# Led_Panel.net
KiCad netlist of a schematic drawn in Altium Designer
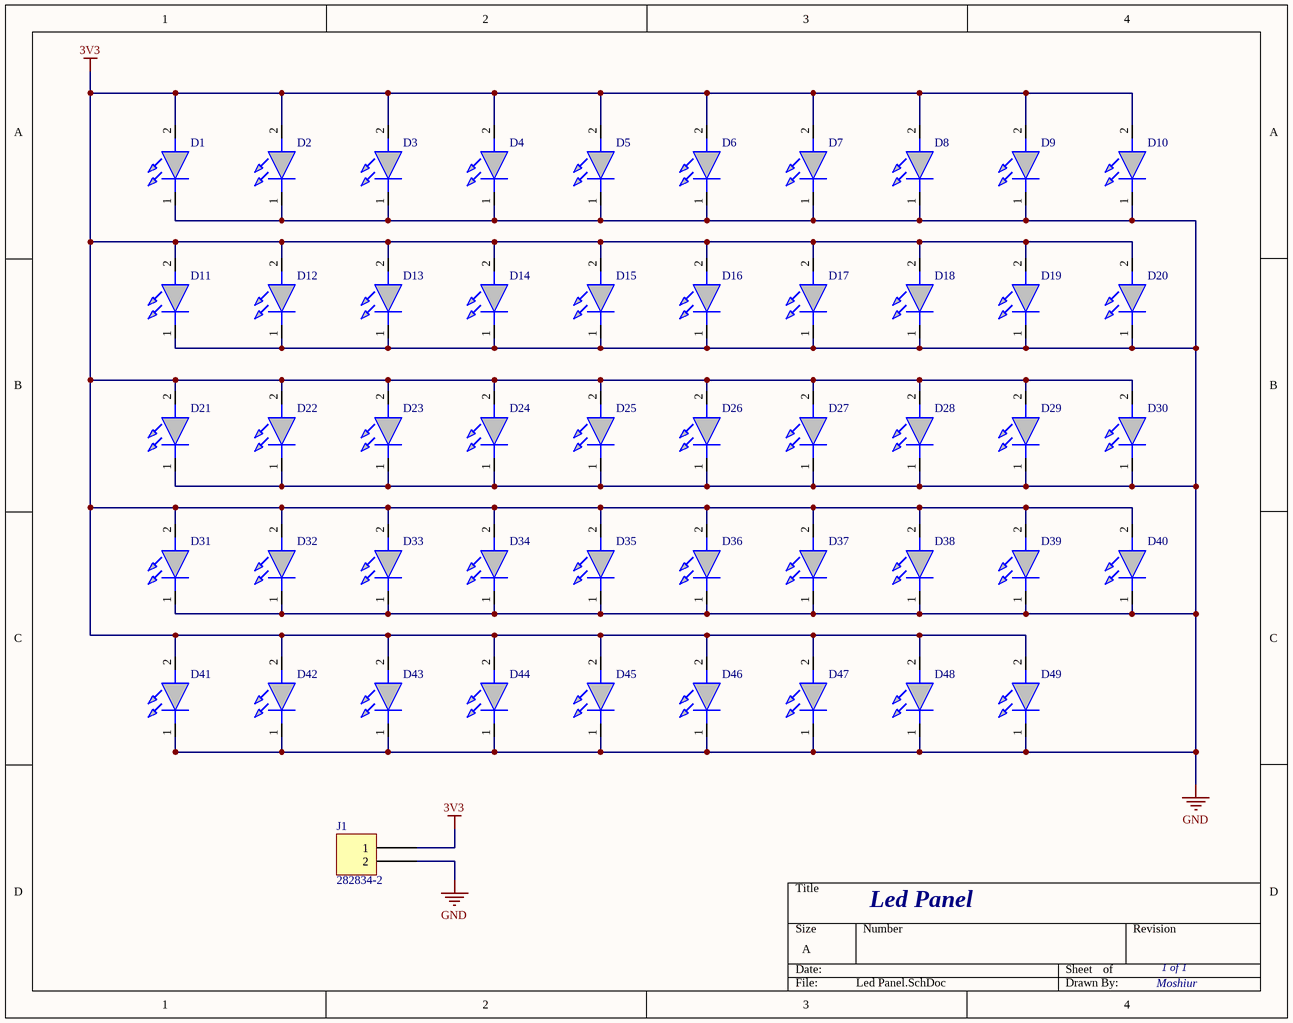
[diagram p0: Led Panel.SchDoc]

(export (version "E")
  (design (tool "Eeschema 10.0.6"))
  (components
    (comp (ref "D1")
      (value "L1IG-0750100000000")
      (footprint "L1IG0750100000000")
      (description "Infrared Emitters - High Power Broadrange IR LED 600 - 1050nm")
      (fields (field (name "MOUSER PART NUMBER") "997-L1IG075010000"))
      (libsource (lib "L1IG-0750100000000") (part "L1IG-0750100000000"))
    )
    (comp (ref "D2")
      (value "L1IG-0750100000000")
      (footprint "L1IG0750100000000")
      (description "Infrared Emitters - High Power Broadrange IR LED 600 - 1050nm")
      (fields (field (name "MOUSER PART NUMBER") "997-L1IG075010000"))
      (libsource (lib "L1IG-0750100000000") (part "L1IG-0750100000000"))
    )
    (comp (ref "D3")
      (value "L1IG-0750100000000")
      (footprint "L1IG0750100000000")
      (description "Infrared Emitters - High Power Broadrange IR LED 600 - 1050nm")
      (fields (field (name "MOUSER PART NUMBER") "997-L1IG075010000"))
      (libsource (lib "L1IG-0750100000000") (part "L1IG-0750100000000"))
    )
    (comp (ref "D4")
      (value "L1IG-0750100000000")
      (footprint "L1IG0750100000000")
      (description "Infrared Emitters - High Power Broadrange IR LED 600 - 1050nm")
      (fields (field (name "MOUSER PART NUMBER") "997-L1IG075010000"))
      (libsource (lib "L1IG-0750100000000") (part "L1IG-0750100000000"))
    )
    (comp (ref "D5")
      (value "L1IG-0750100000000")
      (footprint "L1IG0750100000000")
      (description "Infrared Emitters - High Power Broadrange IR LED 600 - 1050nm")
      (fields (field (name "MOUSER PART NUMBER") "997-L1IG075010000"))
      (libsource (lib "L1IG-0750100000000") (part "L1IG-0750100000000"))
    )
    (comp (ref "D6")
      (value "L1IG-0750100000000")
      (footprint "L1IG0750100000000")
      (description "Infrared Emitters - High Power Broadrange IR LED 600 - 1050nm")
      (fields (field (name "MOUSER PART NUMBER") "997-L1IG075010000"))
      (libsource (lib "L1IG-0750100000000") (part "L1IG-0750100000000"))
    )
    (comp (ref "D7")
      (value "L1IG-0750100000000")
      (footprint "L1IG0750100000000")
      (description "Infrared Emitters - High Power Broadrange IR LED 600 - 1050nm")
      (fields (field (name "MOUSER PART NUMBER") "997-L1IG075010000"))
      (libsource (lib "L1IG-0750100000000") (part "L1IG-0750100000000"))
    )
    (comp (ref "D8")
      (value "L1IG-0750100000000")
      (footprint "L1IG0750100000000")
      (description "Infrared Emitters - High Power Broadrange IR LED 600 - 1050nm")
      (fields (field (name "MOUSER PART NUMBER") "997-L1IG075010000"))
      (libsource (lib "L1IG-0750100000000") (part "L1IG-0750100000000"))
    )
    (comp (ref "D9")
      (value "L1IG-0750100000000")
      (footprint "L1IG0750100000000")
      (description "Infrared Emitters - High Power Broadrange IR LED 600 - 1050nm")
      (fields (field (name "MOUSER PART NUMBER") "997-L1IG075010000"))
      (libsource (lib "L1IG-0750100000000") (part "L1IG-0750100000000"))
    )
    (comp (ref "D10")
      (value "L1IG-0750100000000")
      (footprint "L1IG0750100000000")
      (description "Infrared Emitters - High Power Broadrange IR LED 600 - 1050nm")
      (fields (field (name "MOUSER PART NUMBER") "997-L1IG075010000"))
      (libsource (lib "L1IG-0750100000000") (part "L1IG-0750100000000"))
    )
    (comp (ref "D11")
      (value "L1IG-0750100000000")
      (footprint "L1IG0750100000000")
      (description "Infrared Emitters - High Power Broadrange IR LED 600 - 1050nm")
      (fields (field (name "MOUSER PART NUMBER") "997-L1IG075010000"))
      (libsource (lib "L1IG-0750100000000") (part "L1IG-0750100000000"))
    )
    (comp (ref "D12")
      (value "L1IG-0750100000000")
      (footprint "L1IG0750100000000")
      (description "Infrared Emitters - High Power Broadrange IR LED 600 - 1050nm")
      (fields (field (name "MOUSER PART NUMBER") "997-L1IG075010000"))
      (libsource (lib "L1IG-0750100000000") (part "L1IG-0750100000000"))
    )
    (comp (ref "D13")
      (value "L1IG-0750100000000")
      (footprint "L1IG0750100000000")
      (description "Infrared Emitters - High Power Broadrange IR LED 600 - 1050nm")
      (fields (field (name "MOUSER PART NUMBER") "997-L1IG075010000"))
      (libsource (lib "L1IG-0750100000000") (part "L1IG-0750100000000"))
    )
    (comp (ref "D14")
      (value "L1IG-0750100000000")
      (footprint "L1IG0750100000000")
      (description "Infrared Emitters - High Power Broadrange IR LED 600 - 1050nm")
      (fields (field (name "MOUSER PART NUMBER") "997-L1IG075010000"))
      (libsource (lib "L1IG-0750100000000") (part "L1IG-0750100000000"))
    )
    (comp (ref "D15")
      (value "L1IG-0750100000000")
      (footprint "L1IG0750100000000")
      (description "Infrared Emitters - High Power Broadrange IR LED 600 - 1050nm")
      (fields (field (name "MOUSER PART NUMBER") "997-L1IG075010000"))
      (libsource (lib "L1IG-0750100000000") (part "L1IG-0750100000000"))
    )
    (comp (ref "D16")
      (value "L1IG-0750100000000")
      (footprint "L1IG0750100000000")
      (description "Infrared Emitters - High Power Broadrange IR LED 600 - 1050nm")
      (fields (field (name "MOUSER PART NUMBER") "997-L1IG075010000"))
      (libsource (lib "L1IG-0750100000000") (part "L1IG-0750100000000"))
    )
    (comp (ref "D17")
      (value "L1IG-0750100000000")
      (footprint "L1IG0750100000000")
      (description "Infrared Emitters - High Power Broadrange IR LED 600 - 1050nm")
      (fields (field (name "MOUSER PART NUMBER") "997-L1IG075010000"))
      (libsource (lib "L1IG-0750100000000") (part "L1IG-0750100000000"))
    )
    (comp (ref "D18")
      (value "L1IG-0750100000000")
      (footprint "L1IG0750100000000")
      (description "Infrared Emitters - High Power Broadrange IR LED 600 - 1050nm")
      (fields (field (name "MOUSER PART NUMBER") "997-L1IG075010000"))
      (libsource (lib "L1IG-0750100000000") (part "L1IG-0750100000000"))
    )
    (comp (ref "D19")
      (value "L1IG-0750100000000")
      (footprint "L1IG0750100000000")
      (description "Infrared Emitters - High Power Broadrange IR LED 600 - 1050nm")
      (fields (field (name "MOUSER PART NUMBER") "997-L1IG075010000"))
      (libsource (lib "L1IG-0750100000000") (part "L1IG-0750100000000"))
    )
    (comp (ref "D20")
      (value "L1IG-0750100000000")
      (footprint "L1IG0750100000000")
      (description "Infrared Emitters - High Power Broadrange IR LED 600 - 1050nm")
      (fields (field (name "MOUSER PART NUMBER") "997-L1IG075010000"))
      (libsource (lib "L1IG-0750100000000") (part "L1IG-0750100000000"))
    )
    (comp (ref "D21")
      (value "L1IG-0750100000000")
      (footprint "L1IG0750100000000")
      (description "Infrared Emitters - High Power Broadrange IR LED 600 - 1050nm")
      (fields (field (name "MOUSER PART NUMBER") "997-L1IG075010000"))
      (libsource (lib "L1IG-0750100000000") (part "L1IG-0750100000000"))
    )
    (comp (ref "D22")
      (value "L1IG-0750100000000")
      (footprint "L1IG0750100000000")
      (description "Infrared Emitters - High Power Broadrange IR LED 600 - 1050nm")
      (fields (field (name "MOUSER PART NUMBER") "997-L1IG075010000"))
      (libsource (lib "L1IG-0750100000000") (part "L1IG-0750100000000"))
    )
    (comp (ref "D23")
      (value "L1IG-0750100000000")
      (footprint "L1IG0750100000000")
      (description "Infrared Emitters - High Power Broadrange IR LED 600 - 1050nm")
      (fields (field (name "MOUSER PART NUMBER") "997-L1IG075010000"))
      (libsource (lib "L1IG-0750100000000") (part "L1IG-0750100000000"))
    )
    (comp (ref "D24")
      (value "L1IG-0750100000000")
      (footprint "L1IG0750100000000")
      (description "Infrared Emitters - High Power Broadrange IR LED 600 - 1050nm")
      (fields (field (name "MOUSER PART NUMBER") "997-L1IG075010000"))
      (libsource (lib "L1IG-0750100000000") (part "L1IG-0750100000000"))
    )
    (comp (ref "D25")
      (value "L1IG-0750100000000")
      (footprint "L1IG0750100000000")
      (description "Infrared Emitters - High Power Broadrange IR LED 600 - 1050nm")
      (fields (field (name "MOUSER PART NUMBER") "997-L1IG075010000"))
      (libsource (lib "L1IG-0750100000000") (part "L1IG-0750100000000"))
    )
    (comp (ref "D26")
      (value "L1IG-0750100000000")
      (footprint "L1IG0750100000000")
      (description "Infrared Emitters - High Power Broadrange IR LED 600 - 1050nm")
      (fields (field (name "MOUSER PART NUMBER") "997-L1IG075010000"))
      (libsource (lib "L1IG-0750100000000") (part "L1IG-0750100000000"))
    )
    (comp (ref "D27")
      (value "L1IG-0750100000000")
      (footprint "L1IG0750100000000")
      (description "Infrared Emitters - High Power Broadrange IR LED 600 - 1050nm")
      (fields (field (name "MOUSER PART NUMBER") "997-L1IG075010000"))
      (libsource (lib "L1IG-0750100000000") (part "L1IG-0750100000000"))
    )
    (comp (ref "D28")
      (value "L1IG-0750100000000")
      (footprint "L1IG0750100000000")
      (description "Infrared Emitters - High Power Broadrange IR LED 600 - 1050nm")
      (fields (field (name "MOUSER PART NUMBER") "997-L1IG075010000"))
      (libsource (lib "L1IG-0750100000000") (part "L1IG-0750100000000"))
    )
    (comp (ref "D29")
      (value "L1IG-0750100000000")
      (footprint "L1IG0750100000000")
      (description "Infrared Emitters - High Power Broadrange IR LED 600 - 1050nm")
      (fields (field (name "MOUSER PART NUMBER") "997-L1IG075010000"))
      (libsource (lib "L1IG-0750100000000") (part "L1IG-0750100000000"))
    )
    (comp (ref "D30")
      (value "L1IG-0750100000000")
      (footprint "L1IG0750100000000")
      (description "Infrared Emitters - High Power Broadrange IR LED 600 - 1050nm")
      (fields (field (name "MOUSER PART NUMBER") "997-L1IG075010000"))
      (libsource (lib "L1IG-0750100000000") (part "L1IG-0750100000000"))
    )
    (comp (ref "D31")
      (value "L1IG-0750100000000")
      (footprint "L1IG0750100000000")
      (description "Infrared Emitters - High Power Broadrange IR LED 600 - 1050nm")
      (fields (field (name "MOUSER PART NUMBER") "997-L1IG075010000"))
      (libsource (lib "L1IG-0750100000000") (part "L1IG-0750100000000"))
    )
    (comp (ref "D32")
      (value "L1IG-0750100000000")
      (footprint "L1IG0750100000000")
      (description "Infrared Emitters - High Power Broadrange IR LED 600 - 1050nm")
      (fields (field (name "MOUSER PART NUMBER") "997-L1IG075010000"))
      (libsource (lib "L1IG-0750100000000") (part "L1IG-0750100000000"))
    )
    (comp (ref "D33")
      (value "L1IG-0750100000000")
      (footprint "L1IG0750100000000")
      (description "Infrared Emitters - High Power Broadrange IR LED 600 - 1050nm")
      (fields (field (name "MOUSER PART NUMBER") "997-L1IG075010000"))
      (libsource (lib "L1IG-0750100000000") (part "L1IG-0750100000000"))
    )
    (comp (ref "D34")
      (value "L1IG-0750100000000")
      (footprint "L1IG0750100000000")
      (description "Infrared Emitters - High Power Broadrange IR LED 600 - 1050nm")
      (fields (field (name "MOUSER PART NUMBER") "997-L1IG075010000"))
      (libsource (lib "L1IG-0750100000000") (part "L1IG-0750100000000"))
    )
    (comp (ref "D35")
      (value "L1IG-0750100000000")
      (footprint "L1IG0750100000000")
      (description "Infrared Emitters - High Power Broadrange IR LED 600 - 1050nm")
      (fields (field (name "MOUSER PART NUMBER") "997-L1IG075010000"))
      (libsource (lib "L1IG-0750100000000") (part "L1IG-0750100000000"))
    )
    (comp (ref "D36")
      (value "L1IG-0750100000000")
      (footprint "L1IG0750100000000")
      (description "Infrared Emitters - High Power Broadrange IR LED 600 - 1050nm")
      (fields (field (name "MOUSER PART NUMBER") "997-L1IG075010000"))
      (libsource (lib "L1IG-0750100000000") (part "L1IG-0750100000000"))
    )
    (comp (ref "D37")
      (value "L1IG-0750100000000")
      (footprint "L1IG0750100000000")
      (description "Infrared Emitters - High Power Broadrange IR LED 600 - 1050nm")
      (fields (field (name "MOUSER PART NUMBER") "997-L1IG075010000"))
      (libsource (lib "L1IG-0750100000000") (part "L1IG-0750100000000"))
    )
    (comp (ref "D38")
      (value "L1IG-0750100000000")
      (footprint "L1IG0750100000000")
      (description "Infrared Emitters - High Power Broadrange IR LED 600 - 1050nm")
      (fields (field (name "MOUSER PART NUMBER") "997-L1IG075010000"))
      (libsource (lib "L1IG-0750100000000") (part "L1IG-0750100000000"))
    )
    (comp (ref "D39")
      (value "L1IG-0750100000000")
      (footprint "L1IG0750100000000")
      (description "Infrared Emitters - High Power Broadrange IR LED 600 - 1050nm")
      (fields (field (name "MOUSER PART NUMBER") "997-L1IG075010000"))
      (libsource (lib "L1IG-0750100000000") (part "L1IG-0750100000000"))
    )
    (comp (ref "D40")
      (value "L1IG-0750100000000")
      (footprint "L1IG0750100000000")
      (description "Infrared Emitters - High Power Broadrange IR LED 600 - 1050nm")
      (fields (field (name "MOUSER PART NUMBER") "997-L1IG075010000"))
      (libsource (lib "L1IG-0750100000000") (part "L1IG-0750100000000"))
    )
    (comp (ref "D41")
      (value "L1IG-0750100000000")
      (footprint "L1IG0750100000000")
      (description "Infrared Emitters - High Power Broadrange IR LED 600 - 1050nm")
      (fields (field (name "MOUSER PART NUMBER") "997-L1IG075010000"))
      (libsource (lib "L1IG-0750100000000") (part "L1IG-0750100000000"))
    )
    (comp (ref "D42")
      (value "L1IG-0750100000000")
      (footprint "L1IG0750100000000")
      (description "Infrared Emitters - High Power Broadrange IR LED 600 - 1050nm")
      (fields (field (name "MOUSER PART NUMBER") "997-L1IG075010000"))
      (libsource (lib "L1IG-0750100000000") (part "L1IG-0750100000000"))
    )
    (comp (ref "D43")
      (value "L1IG-0750100000000")
      (footprint "L1IG0750100000000")
      (description "Infrared Emitters - High Power Broadrange IR LED 600 - 1050nm")
      (fields (field (name "MOUSER PART NUMBER") "997-L1IG075010000"))
      (libsource (lib "L1IG-0750100000000") (part "L1IG-0750100000000"))
    )
    (comp (ref "D44")
      (value "L1IG-0750100000000")
      (footprint "L1IG0750100000000")
      (description "Infrared Emitters - High Power Broadrange IR LED 600 - 1050nm")
      (fields (field (name "MOUSER PART NUMBER") "997-L1IG075010000"))
      (libsource (lib "L1IG-0750100000000") (part "L1IG-0750100000000"))
    )
    (comp (ref "D45")
      (value "L1IG-0750100000000")
      (footprint "L1IG0750100000000")
      (description "Infrared Emitters - High Power Broadrange IR LED 600 - 1050nm")
      (fields (field (name "MOUSER PART NUMBER") "997-L1IG075010000"))
      (libsource (lib "L1IG-0750100000000") (part "L1IG-0750100000000"))
    )
    (comp (ref "D46")
      (value "L1IG-0750100000000")
      (footprint "L1IG0750100000000")
      (description "Infrared Emitters - High Power Broadrange IR LED 600 - 1050nm")
      (fields (field (name "MOUSER PART NUMBER") "997-L1IG075010000"))
      (libsource (lib "L1IG-0750100000000") (part "L1IG-0750100000000"))
    )
    (comp (ref "D47")
      (value "L1IG-0750100000000")
      (footprint "L1IG0750100000000")
      (description "Infrared Emitters - High Power Broadrange IR LED 600 - 1050nm")
      (fields (field (name "MOUSER PART NUMBER") "997-L1IG075010000"))
      (libsource (lib "L1IG-0750100000000") (part "L1IG-0750100000000"))
    )
    (comp (ref "D48")
      (value "L1IG-0750100000000")
      (footprint "L1IG0750100000000")
      (description "Infrared Emitters - High Power Broadrange IR LED 600 - 1050nm")
      (fields (field (name "MOUSER PART NUMBER") "997-L1IG075010000"))
      (libsource (lib "L1IG-0750100000000") (part "L1IG-0750100000000"))
    )
    (comp (ref "D49")
      (value "L1IG-0750100000000")
      (footprint "L1IG0750100000000")
      (description "Infrared Emitters - High Power Broadrange IR LED 600 - 1050nm")
      (fields (field (name "MOUSER PART NUMBER") "997-L1IG075010000"))
      (libsource (lib "L1IG-0750100000000") (part "L1IG-0750100000000"))
    )
    (comp (ref "J1")
      (value "282834-2")
      (footprint "TE 282834-2")
      (description "TERM BLK 2P SIDE ENT 2.54MM PCB")
      (fields (field (name "MANUFACTURER") "TE Connectivity AMP Connectors") (field (name "VOLTAGE") "150V"))
      (libsource (lib "Celestial Altium Library - altium_library") (part "2 Pin"))
    )
  )
  (nets
    (net (code "1") (name "3V3") (class "Default")
      (node (ref "D1") (pin "2") (pinfunction "A_2") (pintype "passive"))
      (node (ref "D10") (pin "2") (pinfunction "A_2") (pintype "passive"))
      (node (ref "D11") (pin "2") (pinfunction "A_2") (pintype "passive"))
      (node (ref "D12") (pin "2") (pinfunction "A_2") (pintype "passive"))
      (node (ref "D13") (pin "2") (pinfunction "A_2") (pintype "passive"))
      (node (ref "D14") (pin "2") (pinfunction "A_2") (pintype "passive"))
      (node (ref "D15") (pin "2") (pinfunction "A_2") (pintype "passive"))
      (node (ref "D16") (pin "2") (pinfunction "A_2") (pintype "passive"))
      (node (ref "D17") (pin "2") (pinfunction "A_2") (pintype "passive"))
      (node (ref "D18") (pin "2") (pinfunction "A_2") (pintype "passive"))
      (node (ref "D19") (pin "2") (pinfunction "A_2") (pintype "passive"))
      (node (ref "D2") (pin "2") (pinfunction "A_2") (pintype "passive"))
      (node (ref "D20") (pin "2") (pinfunction "A_2") (pintype "passive"))
      (node (ref "D21") (pin "2") (pinfunction "A_2") (pintype "passive"))
      (node (ref "D22") (pin "2") (pinfunction "A_2") (pintype "passive"))
      (node (ref "D23") (pin "2") (pinfunction "A_2") (pintype "passive"))
      (node (ref "D24") (pin "2") (pinfunction "A_2") (pintype "passive"))
      (node (ref "D25") (pin "2") (pinfunction "A_2") (pintype "passive"))
      (node (ref "D26") (pin "2") (pinfunction "A_2") (pintype "passive"))
      (node (ref "D27") (pin "2") (pinfunction "A_2") (pintype "passive"))
      (node (ref "D28") (pin "2") (pinfunction "A_2") (pintype "passive"))
      (node (ref "D29") (pin "2") (pinfunction "A_2") (pintype "passive"))
      (node (ref "D3") (pin "2") (pinfunction "A_2") (pintype "passive"))
      (node (ref "D30") (pin "2") (pinfunction "A_2") (pintype "passive"))
      (node (ref "D31") (pin "2") (pinfunction "A_2") (pintype "passive"))
      (node (ref "D32") (pin "2") (pinfunction "A_2") (pintype "passive"))
      (node (ref "D33") (pin "2") (pinfunction "A_2") (pintype "passive"))
      (node (ref "D34") (pin "2") (pinfunction "A_2") (pintype "passive"))
      (node (ref "D35") (pin "2") (pinfunction "A_2") (pintype "passive"))
      (node (ref "D36") (pin "2") (pinfunction "A_2") (pintype "passive"))
      (node (ref "D37") (pin "2") (pinfunction "A_2") (pintype "passive"))
      (node (ref "D38") (pin "2") (pinfunction "A_2") (pintype "passive"))
      (node (ref "D39") (pin "2") (pinfunction "A_2") (pintype "passive"))
      (node (ref "D4") (pin "2") (pinfunction "A_2") (pintype "passive"))
      (node (ref "D40") (pin "2") (pinfunction "A_2") (pintype "passive"))
      (node (ref "D41") (pin "2") (pinfunction "A_2") (pintype "passive"))
      (node (ref "D42") (pin "2") (pinfunction "A_2") (pintype "passive"))
      (node (ref "D43") (pin "2") (pinfunction "A_2") (pintype "passive"))
      (node (ref "D44") (pin "2") (pinfunction "A_2") (pintype "passive"))
      (node (ref "D45") (pin "2") (pinfunction "A_2") (pintype "passive"))
      (node (ref "D46") (pin "2") (pinfunction "A_2") (pintype "passive"))
      (node (ref "D47") (pin "2") (pinfunction "A_2") (pintype "passive"))
      (node (ref "D48") (pin "2") (pinfunction "A_2") (pintype "passive"))
      (node (ref "D49") (pin "2") (pinfunction "A_2") (pintype "passive"))
      (node (ref "D5") (pin "2") (pinfunction "A_2") (pintype "passive"))
      (node (ref "D6") (pin "2") (pinfunction "A_2") (pintype "passive"))
      (node (ref "D7") (pin "2") (pinfunction "A_2") (pintype "passive"))
      (node (ref "D8") (pin "2") (pinfunction "A_2") (pintype "passive"))
      (node (ref "D9") (pin "2") (pinfunction "A_2") (pintype "passive"))
      (node (ref "J1") (pin "1") (pinfunction "1_1") (pintype "passive"))
    )
    (net (code "2") (name "GND") (class "Default")
      (node (ref "D1") (pin "1") (pinfunction "K_1") (pintype "passive"))
      (node (ref "D10") (pin "1") (pinfunction "K_1") (pintype "passive"))
      (node (ref "D11") (pin "1") (pinfunction "K_1") (pintype "passive"))
      (node (ref "D12") (pin "1") (pinfunction "K_1") (pintype "passive"))
      (node (ref "D13") (pin "1") (pinfunction "K_1") (pintype "passive"))
      (node (ref "D14") (pin "1") (pinfunction "K_1") (pintype "passive"))
      (node (ref "D15") (pin "1") (pinfunction "K_1") (pintype "passive"))
      (node (ref "D16") (pin "1") (pinfunction "K_1") (pintype "passive"))
      (node (ref "D17") (pin "1") (pinfunction "K_1") (pintype "passive"))
      (node (ref "D18") (pin "1") (pinfunction "K_1") (pintype "passive"))
      (node (ref "D19") (pin "1") (pinfunction "K_1") (pintype "passive"))
      (node (ref "D2") (pin "1") (pinfunction "K_1") (pintype "passive"))
      (node (ref "D20") (pin "1") (pinfunction "K_1") (pintype "passive"))
      (node (ref "D21") (pin "1") (pinfunction "K_1") (pintype "passive"))
      (node (ref "D22") (pin "1") (pinfunction "K_1") (pintype "passive"))
      (node (ref "D23") (pin "1") (pinfunction "K_1") (pintype "passive"))
      (node (ref "D24") (pin "1") (pinfunction "K_1") (pintype "passive"))
      (node (ref "D25") (pin "1") (pinfunction "K_1") (pintype "passive"))
      (node (ref "D26") (pin "1") (pinfunction "K_1") (pintype "passive"))
      (node (ref "D27") (pin "1") (pinfunction "K_1") (pintype "passive"))
      (node (ref "D28") (pin "1") (pinfunction "K_1") (pintype "passive"))
      (node (ref "D29") (pin "1") (pinfunction "K_1") (pintype "passive"))
      (node (ref "D3") (pin "1") (pinfunction "K_1") (pintype "passive"))
      (node (ref "D30") (pin "1") (pinfunction "K_1") (pintype "passive"))
      (node (ref "D31") (pin "1") (pinfunction "K_1") (pintype "passive"))
      (node (ref "D32") (pin "1") (pinfunction "K_1") (pintype "passive"))
      (node (ref "D33") (pin "1") (pinfunction "K_1") (pintype "passive"))
      (node (ref "D34") (pin "1") (pinfunction "K_1") (pintype "passive"))
      (node (ref "D35") (pin "1") (pinfunction "K_1") (pintype "passive"))
      (node (ref "D36") (pin "1") (pinfunction "K_1") (pintype "passive"))
      (node (ref "D37") (pin "1") (pinfunction "K_1") (pintype "passive"))
      (node (ref "D38") (pin "1") (pinfunction "K_1") (pintype "passive"))
      (node (ref "D39") (pin "1") (pinfunction "K_1") (pintype "passive"))
      (node (ref "D4") (pin "1") (pinfunction "K_1") (pintype "passive"))
      (node (ref "D40") (pin "1") (pinfunction "K_1") (pintype "passive"))
      (node (ref "D41") (pin "1") (pinfunction "K_1") (pintype "passive"))
      (node (ref "D42") (pin "1") (pinfunction "K_1") (pintype "passive"))
      (node (ref "D43") (pin "1") (pinfunction "K_1") (pintype "passive"))
      (node (ref "D44") (pin "1") (pinfunction "K_1") (pintype "passive"))
      (node (ref "D45") (pin "1") (pinfunction "K_1") (pintype "passive"))
      (node (ref "D46") (pin "1") (pinfunction "K_1") (pintype "passive"))
      (node (ref "D47") (pin "1") (pinfunction "K_1") (pintype "passive"))
      (node (ref "D48") (pin "1") (pinfunction "K_1") (pintype "passive"))
      (node (ref "D49") (pin "1") (pinfunction "K_1") (pintype "passive"))
      (node (ref "D5") (pin "1") (pinfunction "K_1") (pintype "passive"))
      (node (ref "D6") (pin "1") (pinfunction "K_1") (pintype "passive"))
      (node (ref "D7") (pin "1") (pinfunction "K_1") (pintype "passive"))
      (node (ref "D8") (pin "1") (pinfunction "K_1") (pintype "passive"))
      (node (ref "D9") (pin "1") (pinfunction "K_1") (pintype "passive"))
      (node (ref "J1") (pin "2") (pinfunction "2_2") (pintype "passive"))
    )
  )
)
